# connectors-interface.net
KiCad netlist of a schematic drawn in Altium Designer
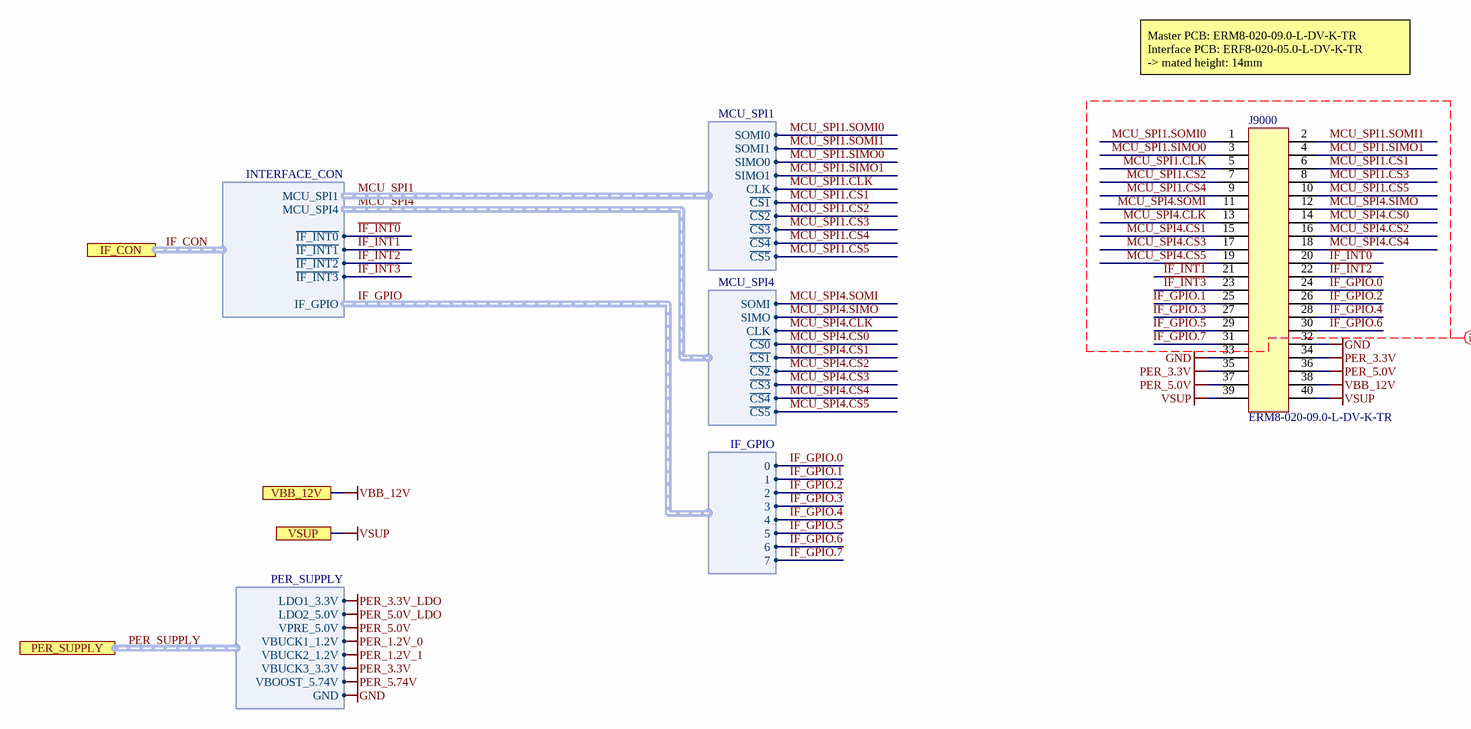
[diagram p0: connectors-interface.SchDoc]

(export (version "E")
  (design (tool "Eeschema 10.0.6"))
  (components
    (comp (ref "J9000")
      (value "ERM8-020-09.0-L-DV-K-TR")
      (footprint "SAMTEC_ERM8-020-09.0-L-DV-K")
      (description "Edge Rate rugged high-speed connector strips")
      (fields
        (field (name "PART NUMBER") "SAMTEC_ERM8-020-09.0-L-DV-K-TR")
        (field (name "MANUFACTURER") "Samtec")
      )
      (libsource (lib "OE750") (part "SAMTEC_ERM8-020-09.0-L-DV-K"))
    )
  )
  (nets
    (net (code "6") (name "/IF_GPIO.0") (class "Default") (node (ref "J9000") (pin "24") (pintype "passive")))
    (net (code "7") (name "/IF_GPIO.1") (class "Default") (node (ref "J9000") (pin "25") (pintype "passive")))
    (net (code "8") (name "/IF_GPIO.2") (class "Default") (node (ref "J9000") (pin "26") (pintype "passive")))
    (net (code "9") (name "/IF_GPIO.3") (class "Default") (node (ref "J9000") (pin "27") (pintype "passive")))
    (net (code "10") (name "/IF_GPIO.4") (class "Default")
      (node (ref "J9000") (pin "28") (pintype "passive"))
    )
    (net (code "11") (name "/IF_GPIO.5") (class "Default")
      (node (ref "J9000") (pin "29") (pintype "passive"))
    )
    (net (code "12") (name "/IF_GPIO.6") (class "Default")
      (node (ref "J9000") (pin "30") (pintype "passive"))
    )
    (net (code "13") (name "/IF_GPIO.7") (class "Default")
      (node (ref "J9000") (pin "31") (pintype "passive"))
    )
    (net (code "15") (name "/IF_INT0") (class "Default") (node (ref "J9000") (pin "20") (pintype "passive")))
    (net (code "16") (name "/IF_INT1") (class "Default") (node (ref "J9000") (pin "21") (pintype "passive")))
    (net (code "17") (name "/IF_INT2") (class "Default") (node (ref "J9000") (pin "22") (pintype "passive")))
    (net (code "18") (name "/IF_INT3") (class "Default") (node (ref "J9000") (pin "23") (pintype "passive")))
    (net (code "19") (name "/MCU_SPI1.CLK") (class "Default")
      (node (ref "J9000") (pin "5") (pintype "passive"))
    )
    (net (code "20") (name "/MCU_SPI1.CS1") (class "Default")
      (node (ref "J9000") (pin "6") (pintype "passive"))
    )
    (net (code "21") (name "/MCU_SPI1.CS2") (class "Default")
      (node (ref "J9000") (pin "7") (pintype "passive"))
    )
    (net (code "22") (name "/MCU_SPI1.CS3") (class "Default")
      (node (ref "J9000") (pin "8") (pintype "passive"))
    )
    (net (code "23") (name "/MCU_SPI1.CS4") (class "Default")
      (node (ref "J9000") (pin "9") (pintype "passive"))
    )
    (net (code "24") (name "/MCU_SPI1.CS5") (class "Default")
      (node (ref "J9000") (pin "10") (pintype "passive"))
    )
    (net (code "25") (name "/MCU_SPI1.SIMO0") (class "Default")
      (node (ref "J9000") (pin "3") (pintype "passive"))
    )
    (net (code "26") (name "/MCU_SPI1.SIMO1") (class "Default")
      (node (ref "J9000") (pin "4") (pintype "passive"))
    )
    (net (code "27") (name "/MCU_SPI1.SOMI0") (class "Default")
      (node (ref "J9000") (pin "1") (pintype "passive"))
    )
    (net (code "28") (name "/MCU_SPI1.SOMI1") (class "Default")
      (node (ref "J9000") (pin "2") (pintype "passive"))
    )
    (net (code "30") (name "/MCU_SPI4.CLK") (class "Default")
      (node (ref "J9000") (pin "13") (pintype "passive"))
    )
    (net (code "31") (name "/MCU_SPI4.CS0") (class "Default")
      (node (ref "J9000") (pin "14") (pintype "passive"))
    )
    (net (code "32") (name "/MCU_SPI4.CS1") (class "Default")
      (node (ref "J9000") (pin "15") (pintype "passive"))
    )
    (net (code "33") (name "/MCU_SPI4.CS2") (class "Default")
      (node (ref "J9000") (pin "16") (pintype "passive"))
    )
    (net (code "34") (name "/MCU_SPI4.CS3") (class "Default")
      (node (ref "J9000") (pin "17") (pintype "passive"))
    )
    (net (code "35") (name "/MCU_SPI4.CS4") (class "Default")
      (node (ref "J9000") (pin "18") (pintype "passive"))
    )
    (net (code "36") (name "/MCU_SPI4.CS5") (class "Default")
      (node (ref "J9000") (pin "19") (pintype "passive"))
    )
    (net (code "37") (name "/MCU_SPI4.SIMO") (class "Default")
      (node (ref "J9000") (pin "12") (pintype "passive"))
    )
    (net (code "38") (name "/MCU_SPI4.SOMI") (class "Default")
      (node (ref "J9000") (pin "11") (pintype "passive"))
    )
    (net (code "42") (name "GND") (class "Default")
      (node (ref "J9000") (pin "32") (pintype "passive"))
      (node (ref "J9000") (pin "33") (pintype "passive"))
    )
    (net (code "45") (name "PER_3.3V") (class "Default")
      (node (ref "J9000") (pin "34") (pintype "passive"))
      (node (ref "J9000") (pin "35") (pintype "passive"))
    )
    (net (code "47") (name "PER_5.0V") (class "Default")
      (node (ref "J9000") (pin "36") (pintype "passive"))
      (node (ref "J9000") (pin "37") (pintype "passive"))
    )
    (net (code "50") (name "VBB_12V") (class "Default") (node (ref "J9000") (pin "38") (pintype "passive")))
    (net (code "51") (name "VSUP") (class "Default")
      (node (ref "J9000") (pin "39") (pintype "passive"))
      (node (ref "J9000") (pin "40") (pintype "passive"))
    )
  )
)
